# Connectors.net
KiCad netlist of a schematic drawn in Altium Designer
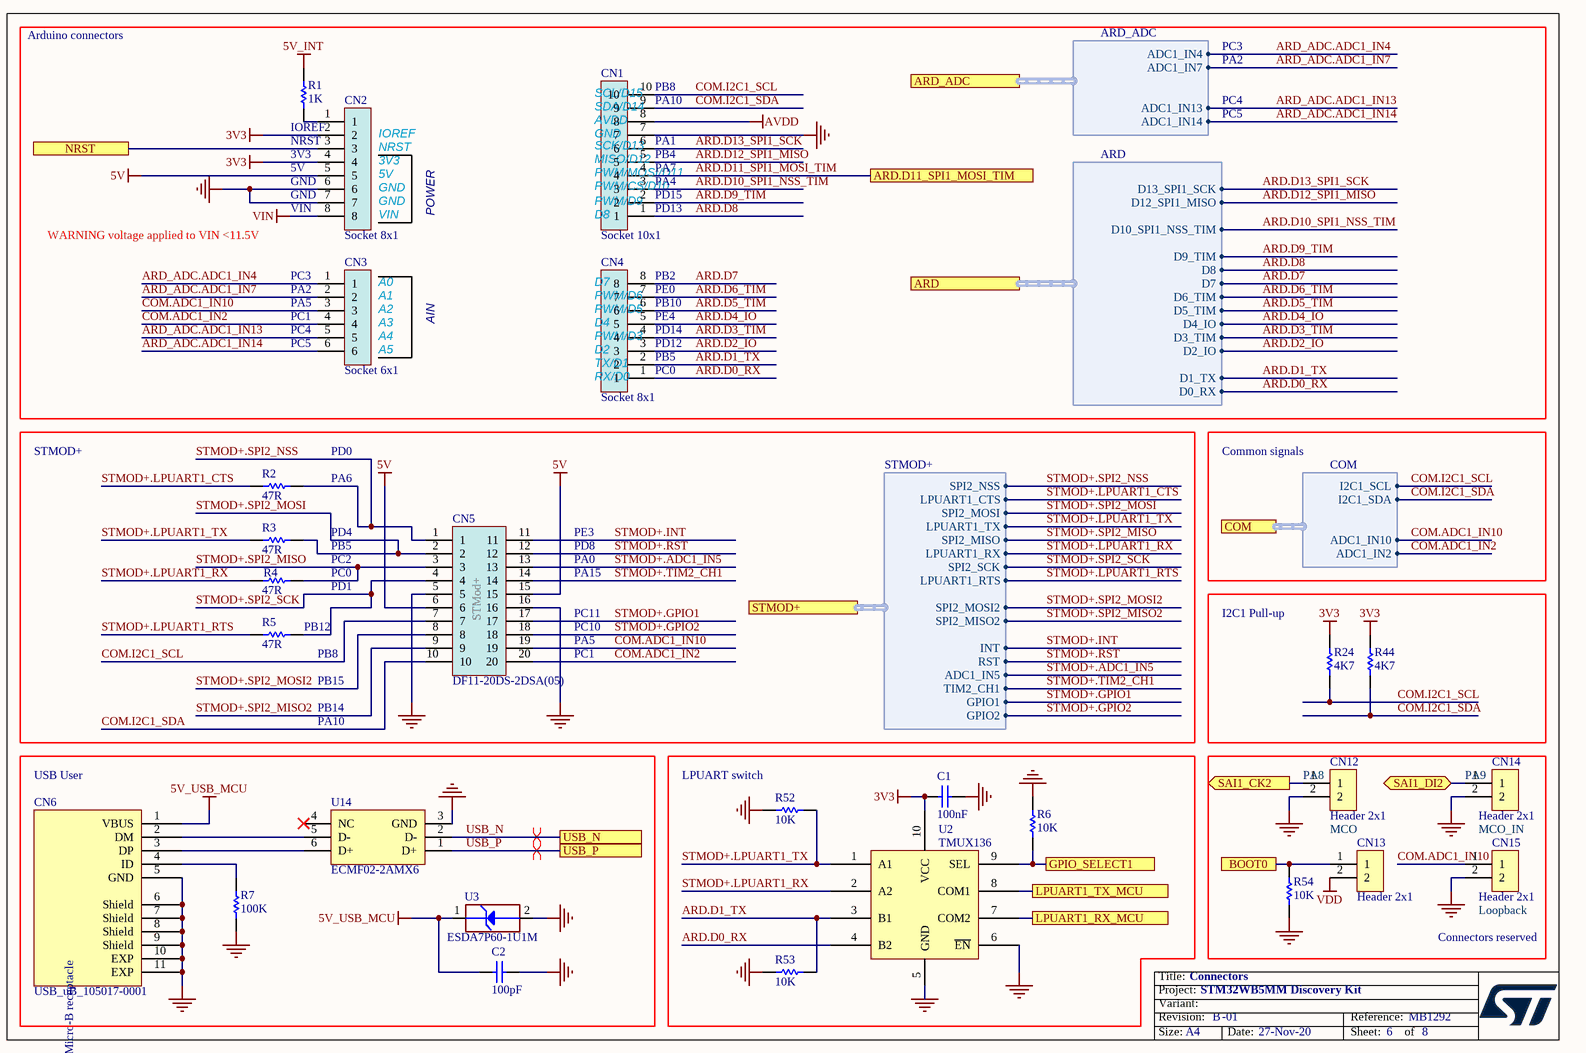
[diagram p0: Connectors.SchDoc]

(export (version "E")
  (design (tool "Eeschema 10.0.6"))
  (components
    (comp (ref "C1")
      (value "100nF")
      (footprint "C0603")
      (description "Capacitor, MLCC, 100nF, 6V3, X5R, 10%, 0603, T=0,8mm")
      (fields (field (name "INTERNAL_PART_NUMBER") "MCD-02119") (field (name "MANUFACTURER") "KEMET"))
      (libsource (lib "MCD_PARTS_database") (part "Capacitor"))
    )
    (comp (ref "C2")
      (value "100pF")
      (footprint "C0603_H0P8")
      (description "Capacitor,MLCC,100pF 50V,NPO,+/-5%, 0603,T=0,8mm")
      (fields
        (field (name "INTERNAL_PART_NUMBER") "MCD-01648")
        (field (name "MANUFACTURER_PART_NUMBER") "CC0603JRNPO9BN101")
      )
      (libsource (lib "MCD_PARTS_database") (part "Capacitor"))
    )
    (comp (ref "CN1")
      (value "Socket 10x1")
      (footprint "CON_SAMTEC_SSW-110-22-X-S-VS")
      (description "Socket, 10x1, 2.54mm, VR, SMT, Height 9.78mm")
      (fields
        (field (name "INTERNAL_PART_NUMBER") "MCD-00301")
        (field (name "MANUFACTURER_PART_NUMBER") "SSW-110-22-L-S-VS")
      )
      (libsource (lib "MCD_PARTS_database") (part "Socket 10x1"))
    )
    (comp (ref "CN2")
      (value "Socket 8x1")
      (footprint "CON_SAMTEC_SSW-108-22-X-S-VS")
      (description "Socket, 8x1, 2.54mm, VR, SMT, Height 9.78mm")
      (fields
        (field (name "INTERNAL_PART_NUMBER") "MCD-00300")
        (field (name "MANUFACTURER_PART_NUMBER") "SSW-108-22-L-S-VS")
      )
      (libsource (lib "MCD_PARTS_database") (part "Socket 8x1"))
    )
    (comp (ref "CN3")
      (value "Socket 6x1")
      (footprint "CON_SAMTEC_SSW-106-22-X-S-VS")
      (description "Socket, 6x1, 2.54mm, VR, SMT, Height 9.78mm")
      (fields
        (field (name "INTERNAL_PART_NUMBER") "MCD-00299")
        (field (name "MANUFACTURER_PART_NUMBER") "SSW-106-22-L-S-VS")
      )
      (libsource (lib "MCD_PARTS_database") (part "Socket 6x1"))
    )
    (comp (ref "CN4")
      (value "Socket 8x1")
      (footprint "CON_SAMTEC_SSW-108-22-X-S-VS")
      (description "Socket, 8x1, 2.54mm, VR, SMT, Height 9.78mm")
      (fields
        (field (name "INTERNAL_PART_NUMBER") "MCD-00300")
        (field (name "MANUFACTURER_PART_NUMBER") "SSW-108-22-L-S-VS")
      )
      (libsource (lib "") (part "Socket 8x1_1"))
    )
    (comp (ref "CN5")
      (value "DF11-20DS-2DSA(05)")
      (footprint "CON_HRS_DF11-20DS-2DSA-XX_SMT-PCB-SIDE__STMOD+")
      (description "Socket, 10x2, 2mm, Straight,SMT, height 9.2mm")
      (fields
        (field (name "INTERNAL_PART_NUMBER") "MCD-02116")
        (field (name "MANUFACTURER_PART_NUMBER") "DF11-20DS-2DSA(06)")
      )
      (libsource (lib "MCD_PARTS_database") (part "Socket 10X2 STMod+"))
    )
    (comp (ref "CN6")
      (value "USB_uB_105017-0001")
      (footprint "CON_USBMICROB_MOLEX_105017-0001_H2P90")
      (description "USB-MICRO-B, 0.65mm, RA, SMT, Bottom Mount,")
      (fields
        (field (name "INTERNAL_PART_NUMBER") "MCD-00028")
        (field (name "MANUFACTURER_PART_NUMBER") "1050170001")
      )
      (libsource (lib "MCD_PARTS_database") (part "USB_uB_105017.0001"))
    )
    (comp (ref "CN12")
      (value "Header 2x1")
      (footprint "CON_LYCONN_313102S141346")
      (description "Header 2x1, 2.54mm, VR, TH, height 5.84mm/5.08 mm, height total 13.46 mm")
      (fields
        (field (name "INTERNAL_PART_NUMBER") "MCD-01668")
        (field (name "MANUFACTURER_PART_NUMBER") "313102S141346")
      )
      (libsource (lib "MCD_PARTS_database") (part "Header 2x1"))
    )
    (comp (ref "CN13")
      (value "Header 2x1")
      (footprint "CON_LYCONN_313102S141346")
      (description "Header 2x1, 2.54mm, VR, TH, height 5.84mm/5.08 mm, height total 13.46 mm")
      (fields
        (field (name "INTERNAL_PART_NUMBER") "MCD-01668")
        (field (name "MANUFACTURER_PART_NUMBER") "313102S141346")
      )
      (libsource (lib "MCD_PARTS_database") (part "Header 2x1"))
    )
    (comp (ref "CN14")
      (value "Header 2x1")
      (footprint "CON_LYCONN_313102S141346")
      (description "Header 2x1, 2.54mm, VR, TH, height 5.84mm/5.08 mm, height total 13.46 mm")
      (fields
        (field (name "INTERNAL_PART_NUMBER") "MCD-01668")
        (field (name "MANUFACTURER_PART_NUMBER") "313102S141346")
      )
      (libsource (lib "MCD_PARTS_database") (part "Header 2x1"))
    )
    (comp (ref "CN15")
      (value "Header 2x1")
      (footprint "CON_LYCONN_313102S141346")
      (description "Header 2x1, 2.54mm, VR, TH, height 5.84mm/5.08 mm, height total 13.46 mm")
      (fields
        (field (name "INTERNAL_PART_NUMBER") "MCD-01668")
        (field (name "MANUFACTURER_PART_NUMBER") "313102S141346")
      )
      (libsource (lib "MCD_PARTS_database") (part "Header 2x1"))
    )
    (comp (ref "R1")
      (value "1K")
      (footprint "R0402")
      (description "Resistor,1K,0402,1%,1/16W")
      (fields
        (field (name "INTERNAL_PART_NUMBER") "MCD-00061")
        (field (name "MANUFACTURER_PART_NUMBER") "RC0402FR-071KL")
      )
      (libsource (lib "MCD_PARTS_database") (part "Resistor"))
    )
    (comp (ref "R2")
      (value "47R")
      (footprint "R0402")
      (description "Resistor,47R,0402,1%,1/16W")
      (fields
        (field (name "INTERNAL_PART_NUMBER") "MCD-00481")
        (field (name "MANUFACTURER_PART_NUMBER") "RC0402FR-0747RL")
      )
      (libsource (lib "MCD_PARTS_database") (part "Resistor"))
    )
    (comp (ref "R3")
      (value "47R")
      (footprint "R0402")
      (description "Resistor,47R,0402,1%,1/16W")
      (fields
        (field (name "INTERNAL_PART_NUMBER") "MCD-00481")
        (field (name "MANUFACTURER_PART_NUMBER") "RC0402FR-0747RL")
      )
      (libsource (lib "MCD_PARTS_database") (part "Resistor"))
    )
    (comp (ref "R4")
      (value "47R")
      (footprint "R0402")
      (description "Resistor,47R,0402,1%,1/16W")
      (fields
        (field (name "INTERNAL_PART_NUMBER") "MCD-00481")
        (field (name "MANUFACTURER_PART_NUMBER") "RC0402FR-0747RL")
      )
      (libsource (lib "MCD_PARTS_database") (part "Resistor"))
    )
    (comp (ref "R5")
      (value "47R")
      (footprint "R0402")
      (description "Resistor,47R,0402,1%,1/16W")
      (fields
        (field (name "INTERNAL_PART_NUMBER") "MCD-00481")
        (field (name "MANUFACTURER_PART_NUMBER") "RC0402FR-0747RL")
      )
      (libsource (lib "MCD_PARTS_database") (part "Resistor"))
    )
    (comp (ref "R6")
      (value "10K")
      (footprint "R0402")
      (description "Resistor,10K,0402,1%,1/16W")
      (fields
        (field (name "INTERNAL_PART_NUMBER") "MCD-00053")
        (field (name "MANUFACTURER_PART_NUMBER") "RC0402FR-0710KL")
      )
      (libsource (lib "MCD_PARTS_database") (part "Resistor"))
    )
    (comp (ref "R7")
      (value "100K")
      (footprint "R0402")
      (description "Resistor,100K,0402,1%,1/16W")
      (fields
        (field (name "INTERNAL_PART_NUMBER") "MCD-00059")
        (field (name "MANUFACTURER_PART_NUMBER") "RC0402FR-07100KL")
      )
      (libsource (lib "MCD_PARTS_database") (part "Resistor"))
    )
    (comp (ref "R24")
      (value "4K7")
      (footprint "R0603")
      (description "Resistor,4K7,0603,1%,1/10W")
      (fields
        (field (name "INTERNAL_PART_NUMBER") "MCD-00219")
        (field (name "MANUFACTURER_PART_NUMBER") "RC0603FR-074K7L")
      )
      (libsource (lib "MCD_PARTS_database") (part "Resistor"))
    )
    (comp (ref "R44")
      (value "4K7")
      (footprint "R0603")
      (description "Resistor,4K7,0603,1%,1/10W")
      (fields
        (field (name "INTERNAL_PART_NUMBER") "MCD-00219")
        (field (name "MANUFACTURER_PART_NUMBER") "RC0603FR-074K7L")
      )
      (libsource (lib "MCD_PARTS_database") (part "Resistor"))
    )
    (comp (ref "R52")
      (value "10K")
      (footprint "R0402")
      (description "Resistor,10K,0402,1%,1/16W")
      (fields
        (field (name "INTERNAL_PART_NUMBER") "MCD-00053")
        (field (name "MANUFACTURER_PART_NUMBER") "RC0402FR-0710KL")
      )
      (libsource (lib "MCD_PARTS_database") (part "Resistor"))
    )
    (comp (ref "R53")
      (value "10K")
      (footprint "R0402")
      (description "Resistor,10K,0402,1%,1/16W")
      (fields
        (field (name "INTERNAL_PART_NUMBER") "MCD-00053")
        (field (name "MANUFACTURER_PART_NUMBER") "RC0402FR-0710KL")
      )
      (libsource (lib "MCD_PARTS_database") (part "Resistor"))
    )
    (comp (ref "R54")
      (value "10K")
      (footprint "R0402")
      (description "Resistor,10K,0402,1%,1/16W")
      (fields
        (field (name "INTERNAL_PART_NUMBER") "MCD-00053")
        (field (name "MANUFACTURER_PART_NUMBER") "RC0402FR-0710KL")
      )
      (libsource (lib "MCD_PARTS_database") (part "Resistor"))
    )
    (comp (ref "U2")
      (value "TMUX136")
      (footprint "ICC_UQFN10_RSE_R-PUQFN-N10_1P5X2_P050")
      (description "6-GHz, 2-Channel, 2:1 Switch, With Power-off Isolation")
      (fields
        (field (name "INTERNAL_PART_NUMBER") "MCD-01847")
        (field (name "MANUFACTURER") "TEXAS INSTRUMENTS")
      )
      (libsource (lib "MCD_PARTS_database") (part "TMUX136"))
    )
    (comp (ref "U3")
      (value "ESDA7P60-1U1M")
      (footprint "ESD_QFN2_1P6X1_P125")
      (description "High power transient voltage suppressor, 7V breakdown")
      (fields
        (field (name "INTERNAL_PART_NUMBER") "MCD-00251")
        (field (name "MANUFACTURER") "STMICROELECTRONICS")
      )
      (libsource (lib "MCD_PARTS_database") (part "ESD-TRANSIL"))
    )
    (comp (ref "U14")
      (value "ECMF02-2AMX6")
      (footprint "ESD_QFN-6L_1P7X1P5_P050")
      (description "Common mode filter with ESD protection for USB 2.0 interface")
      (fields
        (field (name "INTERNAL_PART_NUMBER") "MCD-00649")
        (field (name "MANUFACTURER") "STMICROELECTRONICS")
      )
      (libsource (lib "MCD_PARTS_database") (part "ECMF02-2AMX6"))
    )
  )
  (nets
    (net (code "5") (name "/ARD.D0_RX") (class "Default")
      (node (ref "CN4") (pin "1") (pinfunction "1_1") (pintype "passive"))
      (node (ref "U2") (pin "4") (pinfunction "B2_4") (pintype "passive"))
    )
    (net (code "6") (name "/ARD.D1_TX") (class "Default")
      (node (ref "CN4") (pin "2") (pinfunction "2_2") (pintype "passive"))
      (node (ref "R53") (pin "2") (pinfunction "2_2") (pintype "passive"))
      (node (ref "U2") (pin "3") (pinfunction "B1_3") (pintype "passive"))
    )
    (net (code "7") (name "/ARD.D2_IO") (class "Default")
      (node (ref "CN4") (pin "3") (pinfunction "3_3") (pintype "passive"))
    )
    (net (code "8") (name "/ARD.D3_TIM") (class "Default")
      (node (ref "CN4") (pin "4") (pinfunction "4_4") (pintype "passive"))
    )
    (net (code "9") (name "/ARD.D4_IO") (class "Default")
      (node (ref "CN4") (pin "5") (pinfunction "5_5") (pintype "passive"))
    )
    (net (code "10") (name "/ARD.D5_TIM") (class "Default")
      (node (ref "CN4") (pin "6") (pinfunction "6_6") (pintype "passive"))
    )
    (net (code "11") (name "/ARD.D6_TIM") (class "Default")
      (node (ref "CN4") (pin "7") (pinfunction "7_7") (pintype "passive"))
    )
    (net (code "12") (name "/ARD.D7") (class "Default")
      (node (ref "CN4") (pin "8") (pinfunction "8_8") (pintype "passive"))
    )
    (net (code "13") (name "/ARD.D8") (class "Default")
      (node (ref "CN1") (pin "1") (pinfunction "1_1") (pintype "passive"))
    )
    (net (code "14") (name "/ARD.D9_TIM") (class "Default")
      (node (ref "CN1") (pin "2") (pinfunction "2_2") (pintype "passive"))
    )
    (net (code "15") (name "/ARD.D10_SPI1_NSS_TIM") (class "Default")
      (node (ref "CN1") (pin "3") (pinfunction "3_3") (pintype "passive"))
    )
    (net (code "16") (name "/ARD.D11_SPI1_MOSI_TIM") (class "Default")
      (node (ref "CN1") (pin "4") (pinfunction "4_4") (pintype "passive"))
    )
    (net (code "17") (name "/ARD.D12_SPI1_MISO") (class "Default")
      (node (ref "CN1") (pin "5") (pinfunction "5_5") (pintype "passive"))
    )
    (net (code "18") (name "/ARD.D13_SPI1_SCK") (class "Default")
      (node (ref "CN1") (pin "6") (pinfunction "6_6") (pintype "passive"))
    )
    (net (code "19") (name "/ARD_ADC.ADC1_IN4") (class "Default")
      (node (ref "CN3") (pin "1") (pinfunction "1_1") (pintype "passive"))
    )
    (net (code "20") (name "/ARD_ADC.ADC1_IN7") (class "Default")
      (node (ref "CN3") (pin "2") (pinfunction "2_2") (pintype "passive"))
    )
    (net (code "21") (name "/ARD_ADC.ADC1_IN13") (class "Default")
      (node (ref "CN3") (pin "5") (pinfunction "5_5") (pintype "passive"))
    )
    (net (code "22") (name "/ARD_ADC.ADC1_IN14") (class "Default")
      (node (ref "CN3") (pin "6") (pinfunction "6_6") (pintype "passive"))
    )
    (net (code "23") (name "/BOOT0") (class "Default")
      (node (ref "CN13") (pin "1") (pinfunction "1_1") (pintype "passive"))
      (node (ref "R54") (pin "2") (pinfunction "2_2") (pintype "passive"))
    )
    (net (code "24") (name "/COM.ADC1_IN2") (class "Default")
      (node (ref "CN3") (pin "4") (pinfunction "4_4") (pintype "passive"))
      (node (ref "CN5") (pin "20") (pinfunction "20_20") (pintype "passive"))
    )
    (net (code "25") (name "/COM.ADC1_IN10") (class "Default")
      (node (ref "CN15") (pin "1") (pinfunction "1_1") (pintype "passive"))
      (node (ref "CN3") (pin "3") (pinfunction "3_3") (pintype "passive"))
      (node (ref "CN5") (pin "19") (pinfunction "19_19") (pintype "passive"))
    )
    (net (code "26") (name "/COM.I2C1_SCL") (class "Default")
      (node (ref "CN1") (pin "10") (pinfunction "10_10") (pintype "passive"))
      (node (ref "CN5") (pin "7") (pinfunction "7_7") (pintype "passive"))
      (node (ref "R24") (pin "1") (pinfunction "1_1") (pintype "passive"))
    )
    (net (code "27") (name "/COM.I2C1_SDA") (class "Default")
      (node (ref "CN1") (pin "9") (pinfunction "9_9") (pintype "passive"))
      (node (ref "CN5") (pin "10") (pinfunction "10_10") (pintype "passive"))
      (node (ref "R44") (pin "1") (pinfunction "1_1") (pintype "passive"))
    )
    (net (code "28") (name "/GPIO_SELECT1") (class "Default")
      (node (ref "R6") (pin "1") (pinfunction "1_1") (pintype "passive"))
      (node (ref "U2") (pin "9") (pinfunction "SEL_9") (pintype "passive"))
    )
    (net (code "29") (name "/LPUART1_RX_MCU") (class "Default")
      (node (ref "U2") (pin "7") (pinfunction "COM2_7") (pintype "passive"))
    )
    (net (code "30") (name "/LPUART1_TX_MCU") (class "Default")
      (node (ref "U2") (pin "8") (pinfunction "COM1_8") (pintype "passive"))
    )
    (net (code "31") (name "/NRST") (class "Default")
      (node (ref "CN2") (pin "3") (pinfunction "3_3") (pintype "passive"))
    )
    (net (code "32") (name "/SAI1_CK2") (class "Default")
      (node (ref "CN12") (pin "1") (pinfunction "1_1") (pintype "passive"))
    )
    (net (code "33") (name "/SAI1_DI2") (class "Default")
      (node (ref "CN14") (pin "1") (pinfunction "1_1") (pintype "passive"))
    )
    (net (code "34") (name "/STMOD+.ADC1_IN5") (class "Default")
      (node (ref "CN5") (pin "13") (pinfunction "13_13") (pintype "passive"))
    )
    (net (code "35") (name "/STMOD+.GPIO1") (class "Default")
      (node (ref "CN5") (pin "17") (pinfunction "17_17") (pintype "passive"))
    )
    (net (code "36") (name "/STMOD+.GPIO2") (class "Default")
      (node (ref "CN5") (pin "18") (pinfunction "18_18") (pintype "passive"))
    )
    (net (code "37") (name "/STMOD+.INT") (class "Default")
      (node (ref "CN5") (pin "11") (pinfunction "11_11") (pintype "passive"))
    )
    (net (code "38") (name "/STMOD+.LPUART1_CTS") (class "Default")
      (node (ref "R2") (pin "1") (pinfunction "1_1") (pintype "passive"))
    )
    (net (code "39") (name "/STMOD+.LPUART1_RTS") (class "Default")
      (node (ref "R5") (pin "1") (pinfunction "1_1") (pintype "passive"))
    )
    (net (code "40") (name "/STMOD+.LPUART1_RX") (class "Default")
      (node (ref "R4") (pin "1") (pinfunction "1_1") (pintype "passive"))
      (node (ref "U2") (pin "2") (pinfunction "A2_2") (pintype "passive"))
    )
    (net (code "41") (name "/STMOD+.LPUART1_TX") (class "Default")
      (node (ref "R3") (pin "1") (pinfunction "1_1") (pintype "passive"))
      (node (ref "R52") (pin "2") (pinfunction "2_2") (pintype "passive"))
      (node (ref "U2") (pin "1") (pinfunction "A1_1") (pintype "passive"))
    )
    (net (code "42") (name "/STMOD+.RST") (class "Default")
      (node (ref "CN5") (pin "12") (pinfunction "12_12") (pintype "passive"))
    )
    (net (code "43") (name "/STMOD+.SPI2_MISO") (class "Default")
      (node (ref "CN5") (pin "3") (pinfunction "3_3") (pintype "passive"))
      (node (ref "R4") (pin "2") (pinfunction "2_2") (pintype "passive"))
    )
    (net (code "44") (name "/STMOD+.SPI2_MISO2") (class "Default")
      (node (ref "CN5") (pin "9") (pinfunction "9_9") (pintype "passive"))
    )
    (net (code "45") (name "/STMOD+.SPI2_MOSI") (class "Default")
      (node (ref "CN5") (pin "2") (pinfunction "2_2") (pintype "passive"))
      (node (ref "R3") (pin "2") (pinfunction "2_2") (pintype "passive"))
    )
    (net (code "46") (name "/STMOD+.SPI2_MOSI2") (class "Default")
      (node (ref "CN5") (pin "8") (pinfunction "8_8") (pintype "passive"))
    )
    (net (code "47") (name "/STMOD+.SPI2_NSS") (class "Default")
      (node (ref "CN5") (pin "1") (pinfunction "1_1") (pintype "passive"))
      (node (ref "R2") (pin "2") (pinfunction "2_2") (pintype "passive"))
    )
    (net (code "48") (name "/STMOD+.SPI2_SCK") (class "Default")
      (node (ref "CN5") (pin "4") (pinfunction "4_4") (pintype "passive"))
      (node (ref "R5") (pin "2") (pinfunction "2_2") (pintype "passive"))
    )
    (net (code "49") (name "/STMOD+.TIM2_CH1") (class "Default")
      (node (ref "CN5") (pin "14") (pinfunction "14_14") (pintype "passive"))
    )
    (net (code "50") (name "/USB_N") (class "Default")
      (node (ref "U14") (pin "2") (pinfunction "D-_2") (pintype "passive"))
    )
    (net (code "51") (name "/USB_P") (class "Default")
      (node (ref "U14") (pin "1") (pinfunction "D+_1") (pintype "passive"))
    )
    (net (code "56") (name "3V3") (class "Default")
      (node (ref "C1") (pin "2") (pinfunction "2_2") (pintype "passive"))
      (node (ref "CN2") (pin "2") (pinfunction "2_2") (pintype "passive"))
      (node (ref "CN2") (pin "4") (pinfunction "4_4") (pintype "passive"))
      (node (ref "R24") (pin "2") (pinfunction "2_2") (pintype "passive"))
      (node (ref "R44") (pin "2") (pinfunction "2_2") (pintype "passive"))
      (node (ref "U2") (pin "10") (pinfunction "VCC_10") (pintype "power_in"))
    )
    (net (code "57") (name "5V") (class "Default")
      (node (ref "CN2") (pin "5") (pinfunction "5_5") (pintype "passive"))
      (node (ref "CN5") (pin "15") (pinfunction "15_15") (pintype "passive"))
      (node (ref "CN5") (pin "6") (pinfunction "6_6") (pintype "passive"))
    )
    (net (code "58") (name "5V_INT") (class "Default")
      (node (ref "R1") (pin "2") (pinfunction "2_2") (pintype "passive"))
    )
    (net (code "59") (name "5V_USB_MCU") (class "Default")
      (node (ref "C2") (pin "1") (pinfunction "1_1") (pintype "passive"))
      (node (ref "CN6") (pin "1") (pinfunction "VBUS_1") (pintype "passive"))
      (node (ref "U3") (pin "1") (pinfunction "IO1_1") (pintype "passive"))
    )
    (net (code "60") (name "AVDD") (class "Default")
      (node (ref "CN1") (pin "8") (pinfunction "8_8") (pintype "passive"))
    )
    (net (code "61") (name "GND") (class "Default")
      (node (ref "C1") (pin "1") (pinfunction "1_1") (pintype "passive"))
      (node (ref "C2") (pin "2") (pinfunction "2_2") (pintype "passive"))
      (node (ref "CN1") (pin "7") (pinfunction "7_7") (pintype "passive"))
      (node (ref "CN12") (pin "2") (pinfunction "2_2") (pintype "passive"))
      (node (ref "CN14") (pin "2") (pinfunction "2_2") (pintype "passive"))
      (node (ref "CN15") (pin "2") (pinfunction "2_2") (pintype "passive"))
      (node (ref "CN2") (pin "6") (pinfunction "6_6") (pintype "passive"))
      (node (ref "CN2") (pin "7") (pinfunction "7_7") (pintype "passive"))
      (node (ref "CN5") (pin "16") (pinfunction "16_16") (pintype "passive"))
      (node (ref "CN5") (pin "5") (pinfunction "5_5") (pintype "passive"))
      (node (ref "CN6") (pin "10") (pinfunction "EXP_10") (pintype "passive"))
      (node (ref "CN6") (pin "11") (pinfunction "EXP_11") (pintype "passive"))
      (node (ref "CN6") (pin "5") (pinfunction "GND_5") (pintype "passive"))
      (node (ref "CN6") (pin "6") (pinfunction "Shield_6") (pintype "passive"))
      (node (ref "CN6") (pin "7") (pinfunction "Shield_7") (pintype "passive"))
      (node (ref "CN6") (pin "8") (pinfunction "Shield_8") (pintype "passive"))
      (node (ref "CN6") (pin "9") (pinfunction "Shield_9") (pintype "passive"))
      (node (ref "R52") (pin "1") (pinfunction "1_1") (pintype "passive"))
      (node (ref "R53") (pin "1") (pinfunction "1_1") (pintype "passive"))
      (node (ref "R54") (pin "1") (pinfunction "1_1") (pintype "passive"))
      (node (ref "R6") (pin "2") (pinfunction "2_2") (pintype "passive"))
      (node (ref "R7") (pin "1") (pinfunction "1_1") (pintype "passive"))
      (node (ref "U14") (pin "3") (pinfunction "GND_3") (pintype "passive"))
      (node (ref "U2") (pin "5") (pinfunction "GND_5") (pintype "passive"))
      (node (ref "U2") (pin "6") (pinfunction "~{EN}_6") (pintype "passive"))
      (node (ref "U3") (pin "2") (pinfunction "GND_2") (pintype "passive"))
    )
    (net (code "62") (name "Net-(CN2-Pad1)") (class "Default")
      (node (ref "CN2") (pin "1") (pinfunction "1_1") (pintype "passive"))
      (node (ref "R1") (pin "1") (pinfunction "1_1") (pintype "passive"))
    )
    (net (code "63") (name "Net-(CN6-DM)") (class "Default")
      (node (ref "CN6") (pin "2") (pinfunction "DM_2") (pintype "passive"))
      (node (ref "U14") (pin "5") (pinfunction "D-_5") (pintype "passive"))
    )
    (net (code "64") (name "Net-(CN6-DP)") (class "Default")
      (node (ref "CN6") (pin "3") (pinfunction "DP_3") (pintype "passive"))
      (node (ref "U14") (pin "6") (pinfunction "D+_6") (pintype "passive"))
    )
    (net (code "65") (name "Net-(CN6-ID)") (class "Default")
      (node (ref "CN6") (pin "4") (pinfunction "ID_4") (pintype "passive"))
      (node (ref "R7") (pin "2") (pinfunction "2_2") (pintype "passive"))
    )
    (net (code "66") (name "VDD") (class "Default")
      (node (ref "CN13") (pin "2") (pinfunction "2_2") (pintype "passive"))
    )
    (net (code "67") (name "VIN") (class "Default")
      (node (ref "CN2") (pin "8") (pinfunction "8_8") (pintype "passive"))
    )
    (net (code "68") (name "unconnected-(U14-NC-Pad4)") (class "Default")
      (node (ref "U14") (pin "4") (pinfunction "NC_4") (pintype "passive+no_connect"))
    )
  )
)
